# SH3_-_NUCLEO_HEADERS.net
KiCad netlist of a schematic drawn in Altium Designer
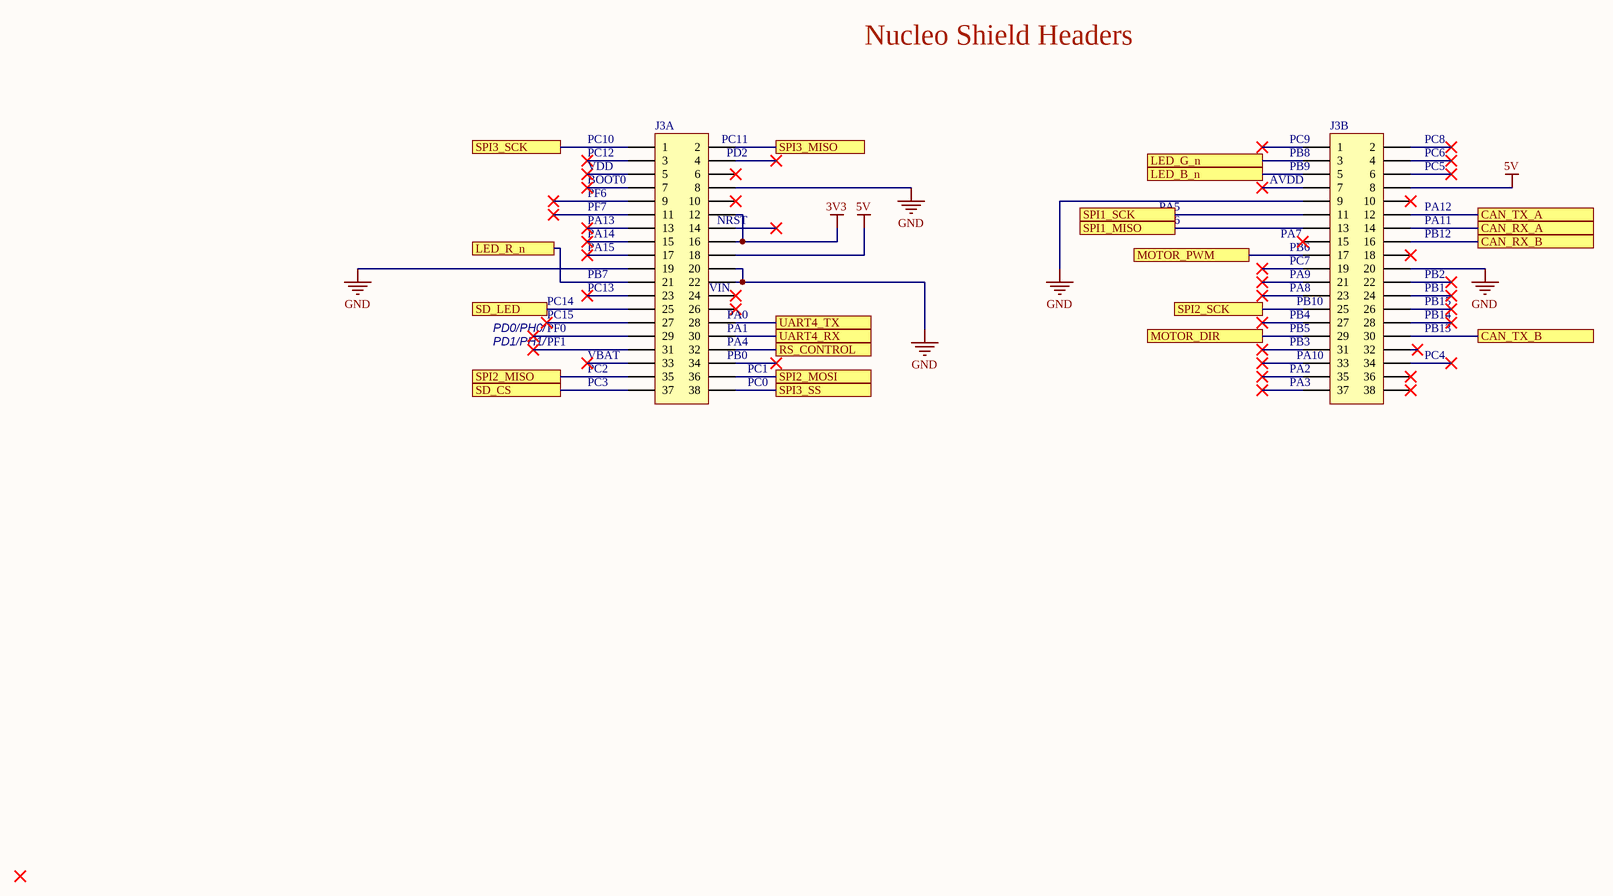
[diagram p0: SH3 - NUCLEO HEADERS.SchDoc]

(export (version "E")
  (design (tool "Eeschema 10.0.6"))
  (components
    (comp (ref "J3")
      (value "HEADER_NUCLEO")
      (footprint "HEADER_NUCLEO")
      (description "CONN HDR 38POS 0.1 GOLD PCB")
      (libsource (lib "UWRT_Schematic_Library_2020") (part "HEADER_NUCLEO"))
    )
  )
  (nets
    (net (code "1") (name "/CAN_RX_A") (class "Default")
      (node (ref "J3") (pin "52") (pinfunction "14_52") (pintype "passive"))
    )
    (net (code "2") (name "/CAN_RX_B") (class "Default")
      (node (ref "J3") (pin "54") (pinfunction "16_54") (pintype "passive"))
    )
    (net (code "3") (name "/CAN_TX_A") (class "Default")
      (node (ref "J3") (pin "50") (pinfunction "12_50") (pintype "passive"))
    )
    (net (code "4") (name "/CAN_TX_B") (class "Default")
      (node (ref "J3") (pin "68") (pinfunction "30_68") (pintype "passive"))
    )
    (net (code "5") (name "/LED_B_n") (class "Default")
      (node (ref "J3") (pin "43") (pinfunction "5_43") (pintype "passive"))
    )
    (net (code "6") (name "/LED_G_n") (class "Default")
      (node (ref "J3") (pin "41") (pinfunction "3_41") (pintype "passive"))
    )
    (net (code "7") (name "/LED_R_n") (class "Default")
      (node (ref "J3") (pin "21") (pinfunction "21_21") (pintype "passive"))
    )
    (net (code "8") (name "/MOTOR_DIR") (class "Default")
      (node (ref "J3") (pin "67") (pinfunction "29_67") (pintype "passive"))
    )
    (net (code "9") (name "/MOTOR_PWM") (class "Default")
      (node (ref "J3") (pin "55") (pinfunction "17_55") (pintype "passive"))
    )
    (net (code "10") (name "/RS_CONTROL") (class "Default")
      (node (ref "J3") (pin "32") (pinfunction "32_32") (pintype "passive"))
    )
    (net (code "11") (name "/SD_CS") (class "Default")
      (node (ref "J3") (pin "37") (pinfunction "37_37") (pintype "passive"))
    )
    (net (code "12") (name "/SD_LED") (class "Default")
      (node (ref "J3") (pin "25") (pinfunction "25_25") (pintype "passive"))
    )
    (net (code "13") (name "/SPI1_MISO") (class "Default")
      (node (ref "J3") (pin "51") (pinfunction "13_51") (pintype "passive"))
    )
    (net (code "14") (name "/SPI1_SCK") (class "Default")
      (node (ref "J3") (pin "49") (pinfunction "11_49") (pintype "passive"))
    )
    (net (code "15") (name "/SPI2_MISO") (class "Default")
      (node (ref "J3") (pin "35") (pinfunction "35_35") (pintype "passive"))
    )
    (net (code "16") (name "/SPI2_MOSI") (class "Default")
      (node (ref "J3") (pin "36") (pinfunction "36_36") (pintype "passive"))
    )
    (net (code "17") (name "/SPI2_SCK") (class "Default")
      (node (ref "J3") (pin "63") (pinfunction "25_63") (pintype "passive"))
    )
    (net (code "18") (name "/SPI3_MISO") (class "Default")
      (node (ref "J3") (pin "2") (pinfunction "2_2") (pintype "passive"))
    )
    (net (code "19") (name "/SPI3_SCK") (class "Default")
      (node (ref "J3") (pin "1") (pinfunction "1_1") (pintype "passive"))
    )
    (net (code "20") (name "/SPI3_SS") (class "Default")
      (node (ref "J3") (pin "38") (pinfunction "38_38") (pintype "passive"))
    )
    (net (code "21") (name "/UART4_RX") (class "Default")
      (node (ref "J3") (pin "30") (pinfunction "30_30") (pintype "passive"))
    )
    (net (code "22") (name "/UART4_TX") (class "Default")
      (node (ref "J3") (pin "28") (pinfunction "28_28") (pintype "passive"))
    )
    (net (code "23") (name "3V3") (class "Default")
      (node (ref "J3") (pin "12") (pinfunction "12_12") (pintype "passive"))
      (node (ref "J3") (pin "16") (pinfunction "16_16") (pintype "passive"))
    )
    (net (code "24") (name "5V") (class "Default")
      (node (ref "J3") (pin "18") (pinfunction "18_18") (pintype "passive"))
      (node (ref "J3") (pin "46") (pinfunction "8_46") (pintype "passive"))
    )
    (net (code "25") (name "GND") (class "Default")
      (node (ref "J3") (pin "19") (pinfunction "19_19") (pintype "passive"))
      (node (ref "J3") (pin "20") (pinfunction "20_20") (pintype "passive"))
      (node (ref "J3") (pin "22") (pinfunction "22_22") (pintype "passive"))
      (node (ref "J3") (pin "47") (pinfunction "9_47") (pintype "passive"))
      (node (ref "J3") (pin "58") (pinfunction "20_58") (pintype "passive"))
      (node (ref "J3") (pin "8") (pinfunction "8_8") (pintype "passive"))
    )
    (net (code "26") (name "unconnected-(J3-Pad3)") (class "Default")
      (node (ref "J3") (pin "3") (pinfunction "3_3") (pintype "passive+no_connect"))
    )
    (net (code "27") (name "unconnected-(J3-Pad4)") (class "Default")
      (node (ref "J3") (pin "4") (pinfunction "4_4") (pintype "passive+no_connect"))
    )
    (net (code "28") (name "unconnected-(J3-Pad5)") (class "Default")
      (node (ref "J3") (pin "5") (pinfunction "5_5") (pintype "passive+no_connect"))
    )
    (net (code "29") (name "unconnected-(J3-Pad6)") (class "Default")
      (node (ref "J3") (pin "6") (pinfunction "6_6") (pintype "passive+no_connect"))
    )
    (net (code "30") (name "unconnected-(J3-Pad7)") (class "Default")
      (node (ref "J3") (pin "7") (pinfunction "7_7") (pintype "passive+no_connect"))
    )
    (net (code "31") (name "unconnected-(J3-Pad9)") (class "Default")
      (node (ref "J3") (pin "9") (pinfunction "9_9") (pintype "passive+no_connect"))
    )
    (net (code "32") (name "unconnected-(J3-Pad10)") (class "Default")
      (node (ref "J3") (pin "10") (pinfunction "10_10") (pintype "passive+no_connect"))
    )
    (net (code "33") (name "unconnected-(J3-Pad11)") (class "Default")
      (node (ref "J3") (pin "11") (pinfunction "11_11") (pintype "passive+no_connect"))
    )
    (net (code "34") (name "unconnected-(J3-Pad13)") (class "Default")
      (node (ref "J3") (pin "13") (pinfunction "13_13") (pintype "passive+no_connect"))
    )
    (net (code "35") (name "unconnected-(J3-Pad14)") (class "Default")
      (node (ref "J3") (pin "14") (pinfunction "14_14") (pintype "passive+no_connect"))
    )
    (net (code "36") (name "unconnected-(J3-Pad15)") (class "Default")
      (node (ref "J3") (pin "15") (pinfunction "15_15") (pintype "passive+no_connect"))
    )
    (net (code "37") (name "unconnected-(J3-Pad17)") (class "Default")
      (node (ref "J3") (pin "17") (pinfunction "17_17") (pintype "passive+no_connect"))
    )
    (net (code "38") (name "unconnected-(J3-Pad23)") (class "Default")
      (node (ref "J3") (pin "23") (pinfunction "23_23") (pintype "passive+no_connect"))
    )
    (net (code "39") (name "unconnected-(J3-Pad24)") (class "Default")
      (node (ref "J3") (pin "24") (pinfunction "24_24") (pintype "passive+no_connect"))
    )
    (net (code "40") (name "unconnected-(J3-Pad26)") (class "Default")
      (node (ref "J3") (pin "26") (pinfunction "26_26") (pintype "passive+no_connect"))
    )
    (net (code "41") (name "unconnected-(J3-Pad27)") (class "Default")
      (node (ref "J3") (pin "27") (pinfunction "27_27") (pintype "passive+no_connect"))
    )
    (net (code "42") (name "unconnected-(J3-Pad29)") (class "Default")
      (node (ref "J3") (pin "29") (pinfunction "29_29") (pintype "passive+no_connect"))
    )
    (net (code "43") (name "unconnected-(J3-Pad31)") (class "Default")
      (node (ref "J3") (pin "31") (pinfunction "31_31") (pintype "passive+no_connect"))
    )
    (net (code "44") (name "unconnected-(J3-Pad33)") (class "Default")
      (node (ref "J3") (pin "33") (pinfunction "33_33") (pintype "passive+no_connect"))
    )
    (net (code "45") (name "unconnected-(J3-Pad34)") (class "Default")
      (node (ref "J3") (pin "34") (pinfunction "34_34") (pintype "passive+no_connect"))
    )
    (net (code "46") (name "unconnected-(J3B-1-Pad39)") (class "Default")
      (node (ref "J3") (pin "39") (pinfunction "1_39") (pintype "passive+no_connect"))
    )
    (net (code "47") (name "unconnected-(J3B-2-Pad40)") (class "Default")
      (node (ref "J3") (pin "40") (pinfunction "2_40") (pintype "passive+no_connect"))
    )
    (net (code "48") (name "unconnected-(J3B-4-Pad42)") (class "Default")
      (node (ref "J3") (pin "42") (pinfunction "4_42") (pintype "passive+no_connect"))
    )
    (net (code "49") (name "unconnected-(J3B-6-Pad44)") (class "Default")
      (node (ref "J3") (pin "44") (pinfunction "6_44") (pintype "passive+no_connect"))
    )
    (net (code "50") (name "unconnected-(J3B-7-Pad45)") (class "Default")
      (node (ref "J3") (pin "45") (pinfunction "7_45") (pintype "passive+no_connect"))
    )
    (net (code "51") (name "unconnected-(J3B-10-Pad48)") (class "Default")
      (node (ref "J3") (pin "48") (pinfunction "10_48") (pintype "passive+no_connect"))
    )
    (net (code "52") (name "unconnected-(J3B-15-Pad53)") (class "Default")
      (node (ref "J3") (pin "53") (pinfunction "15_53") (pintype "passive+no_connect"))
    )
    (net (code "53") (name "unconnected-(J3B-18-Pad56)") (class "Default")
      (node (ref "J3") (pin "56") (pinfunction "18_56") (pintype "passive+no_connect"))
    )
    (net (code "54") (name "unconnected-(J3B-19-Pad57)") (class "Default")
      (node (ref "J3") (pin "57") (pinfunction "19_57") (pintype "passive+no_connect"))
    )
    (net (code "55") (name "unconnected-(J3B-21-Pad59)") (class "Default")
      (node (ref "J3") (pin "59") (pinfunction "21_59") (pintype "passive+no_connect"))
    )
    (net (code "56") (name "unconnected-(J3B-22-Pad60)") (class "Default")
      (node (ref "J3") (pin "60") (pinfunction "22_60") (pintype "passive+no_connect"))
    )
    (net (code "57") (name "unconnected-(J3B-23-Pad61)") (class "Default")
      (node (ref "J3") (pin "61") (pinfunction "23_61") (pintype "passive+no_connect"))
    )
    (net (code "58") (name "unconnected-(J3B-24-Pad62)") (class "Default")
      (node (ref "J3") (pin "62") (pinfunction "24_62") (pintype "passive+no_connect"))
    )
    (net (code "59") (name "unconnected-(J3B-26-Pad64)") (class "Default")
      (node (ref "J3") (pin "64") (pinfunction "26_64") (pintype "passive+no_connect"))
    )
    (net (code "60") (name "unconnected-(J3B-27-Pad65)") (class "Default")
      (node (ref "J3") (pin "65") (pinfunction "27_65") (pintype "passive+no_connect"))
    )
    (net (code "61") (name "unconnected-(J3B-28-Pad66)") (class "Default")
      (node (ref "J3") (pin "66") (pinfunction "28_66") (pintype "passive+no_connect"))
    )
    (net (code "62") (name "unconnected-(J3B-31-Pad69)") (class "Default")
      (node (ref "J3") (pin "69") (pinfunction "31_69") (pintype "passive+no_connect"))
    )
    (net (code "63") (name "unconnected-(J3B-32-Pad70)") (class "Default")
      (node (ref "J3") (pin "70") (pinfunction "32_70") (pintype "passive+no_connect"))
    )
    (net (code "64") (name "unconnected-(J3B-33-Pad71)") (class "Default")
      (node (ref "J3") (pin "71") (pinfunction "33_71") (pintype "passive+no_connect"))
    )
    (net (code "65") (name "unconnected-(J3B-34-Pad72)") (class "Default")
      (node (ref "J3") (pin "72") (pinfunction "34_72") (pintype "passive+no_connect"))
    )
    (net (code "66") (name "unconnected-(J3B-35-Pad73)") (class "Default")
      (node (ref "J3") (pin "73") (pinfunction "35_73") (pintype "passive+no_connect"))
    )
    (net (code "67") (name "unconnected-(J3B-36-Pad74)") (class "Default")
      (node (ref "J3") (pin "74") (pinfunction "36_74") (pintype "passive+no_connect"))
    )
    (net (code "68") (name "unconnected-(J3B-37-Pad75)") (class "Default")
      (node (ref "J3") (pin "75") (pinfunction "37_75") (pintype "passive+no_connect"))
    )
    (net (code "69") (name "unconnected-(J3B-38-Pad76)") (class "Default")
      (node (ref "J3") (pin "76") (pinfunction "38_76") (pintype "passive+no_connect"))
    )
  )
)
